# 03-Actuators.net
KiCad netlist of a schematic drawn in Altium Designer
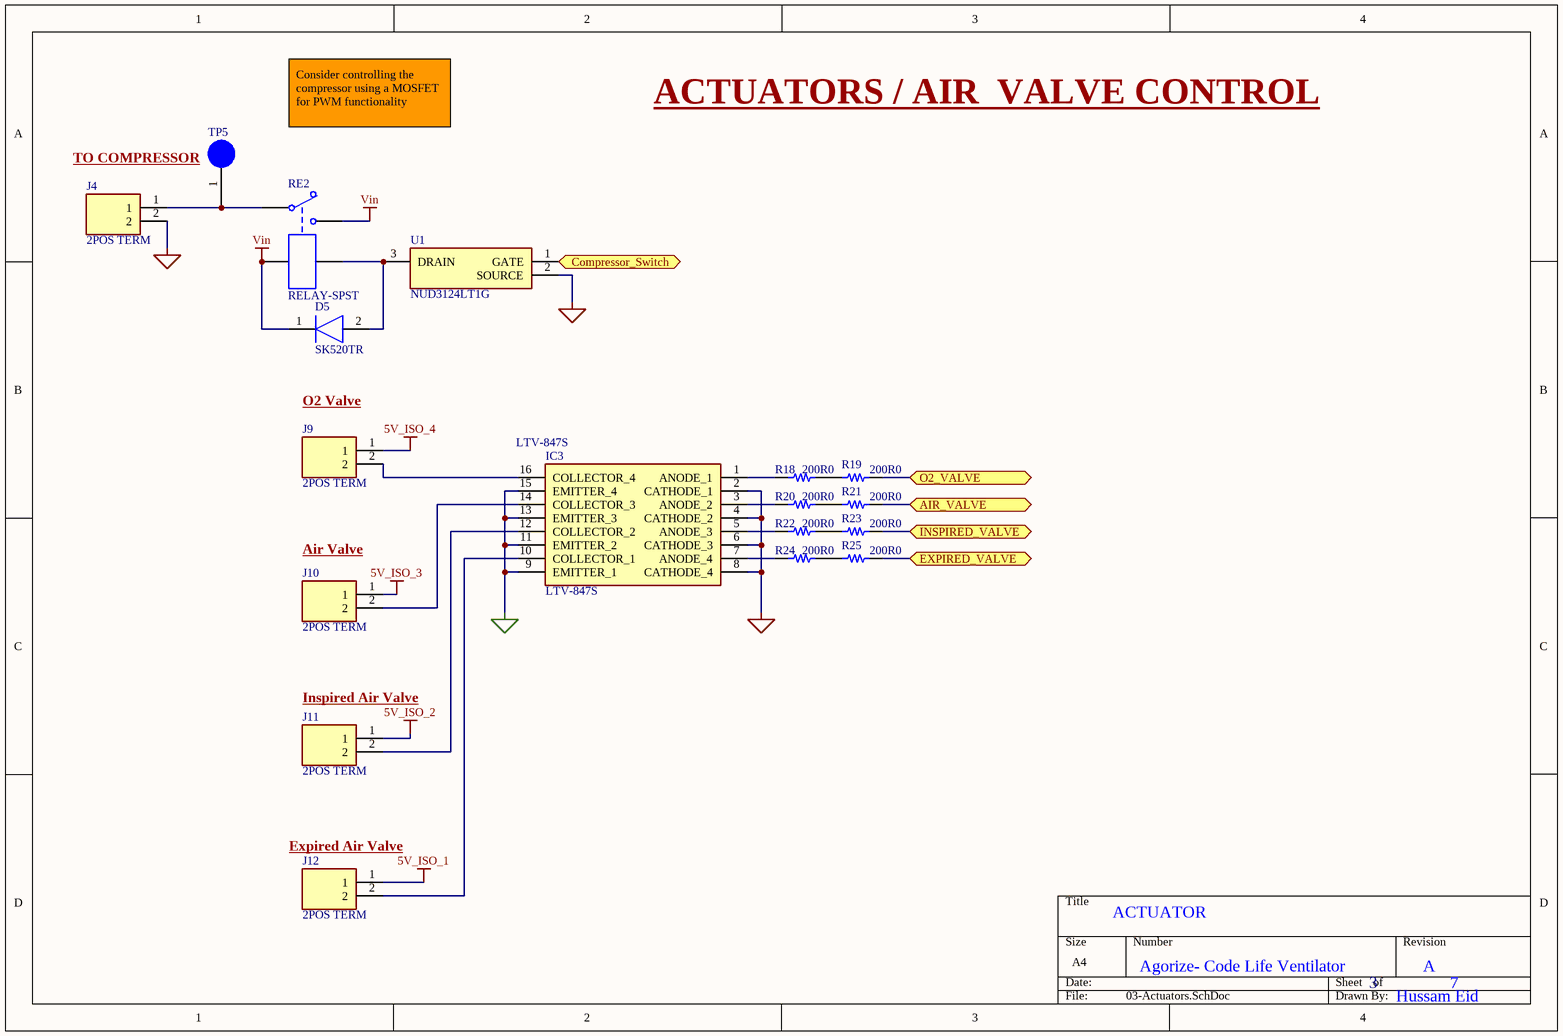
[diagram p0: 03-Actuators.SchDoc]

(export (version "E")
  (design (tool "Eeschema 10.0.6"))
  (components
    (comp (ref "D5")
      (value "SK520TR")
      (footprint "SamacSys:DIOM8060X295N")
      (description "DIODE SCHOTTKY 200V 5A SMC")
      (libsource (lib "*") (part "SK520TR"))
    )
    (comp (ref "IC3")
      (value "LTV-847S")
      (footprint "SamacSys:SOP254P1031X450-16N")
      (description "OPTOISOLTR 5KV 4CH TRANS 16-SMD")
      (fields (field (name "MANUFACTURER PART NUMBER 1") "LTV-847S"))
      (libsource (lib "*") (part "LTV-847S"))
    )
    (comp (ref "J4")
      (value "2POS TERM")
      (footprint "PcbLib1:SHDR2W110P0X500_1X2_1000X830X1140P")
      (description "TERM BLK 2POS SIDE ENTRY 5MM PCB")
      (fields (field (name "VOLTAGE") "300V"))
      (libsource (lib "*") (part "1935161"))
    )
    (comp (ref "J9")
      (value "2POS TERM")
      (footprint "PcbLib1:SHDR2W110P0X500_1X2_1000X830X1140P")
      (description "TERM BLK 2POS SIDE ENTRY 5MM PCB")
      (fields (field (name "VOLTAGE") "300V"))
      (libsource (lib "*") (part "1935161"))
    )
    (comp (ref "J10")
      (value "2POS TERM")
      (footprint "PcbLib1:SHDR2W110P0X500_1X2_1000X830X1140P")
      (description "TERM BLK 2POS SIDE ENTRY 5MM PCB")
      (fields (field (name "VOLTAGE") "300V"))
      (libsource (lib "*") (part "1935161"))
    )
    (comp (ref "J11")
      (value "2POS TERM")
      (footprint "PcbLib1:SHDR2W110P0X500_1X2_1000X830X1140P")
      (description "TERM BLK 2POS SIDE ENTRY 5MM PCB")
      (fields (field (name "VOLTAGE") "300V"))
      (libsource (lib "*") (part "1935161"))
    )
    (comp (ref "J12")
      (value "2POS TERM")
      (footprint "PcbLib1:SHDR2W110P0X500_1X2_1000X830X1140P")
      (description "TERM BLK 2POS SIDE ENTRY 5MM PCB")
      (fields (field (name "VOLTAGE") "300V"))
      (libsource (lib "*") (part "1935161"))
    )
    (comp (ref "R18")
      (value "200R0")
      (footprint "RES 1206/3216")
      (description "RES SMD 10K OHM 1% 1/4W 1206")
      (fields (field (name "TOLERANCE") "1%"))
      (libsource (lib "Celestial Library Database") (part "Resistor"))
    )
    (comp (ref "R19")
      (value "200R0")
      (footprint "RES 1206/3216")
      (description "RES SMD 10K OHM 1% 1/4W 1206")
      (fields (field (name "TOLERANCE") "1%"))
      (libsource (lib "Celestial Library Database") (part "Resistor"))
    )
    (comp (ref "R20")
      (value "200R0")
      (footprint "RES 1206/3216")
      (description "RES SMD 10K OHM 1% 1/4W 1206")
      (fields (field (name "TOLERANCE") "1%"))
      (libsource (lib "Celestial Library Database") (part "Resistor"))
    )
    (comp (ref "R21")
      (value "200R0")
      (footprint "RES 1206/3216")
      (description "RES SMD 10K OHM 1% 1/4W 1206")
      (fields (field (name "TOLERANCE") "1%"))
      (libsource (lib "Celestial Library Database") (part "Resistor"))
    )
    (comp (ref "R22")
      (value "200R0")
      (footprint "RES 1206/3216")
      (description "RES SMD 10K OHM 1% 1/4W 1206")
      (fields (field (name "TOLERANCE") "1%"))
      (libsource (lib "Celestial Library Database") (part "Resistor"))
    )
    (comp (ref "R23")
      (value "200R0")
      (footprint "RES 1206/3216")
      (description "RES SMD 10K OHM 1% 1/4W 1206")
      (fields (field (name "TOLERANCE") "1%"))
      (libsource (lib "Celestial Library Database") (part "Resistor"))
    )
    (comp (ref "R24")
      (value "200R0")
      (footprint "RES 1206/3216")
      (description "RES SMD 10K OHM 1% 1/4W 1206")
      (fields (field (name "TOLERANCE") "1%"))
      (libsource (lib "Celestial Library Database") (part "Resistor"))
    )
    (comp (ref "R25")
      (value "200R0")
      (footprint "RES 1206/3216")
      (description "RES SMD 10K OHM 1% 1/4W 1206")
      (fields (field (name "TOLERANCE") "1%"))
      (libsource (lib "Celestial Library Database") (part "Resistor"))
    )
    (comp (ref "RE2")
      (value "RELAY-SPST")
      (footprint "JSM1A12V4")
      (description "RELAY AUTOMOTIVE SPST 15A 12V")
      (libsource (lib "Schlib1") (part "RELAY-SPST"))
    )
    (comp (ref "TP5")
      (value "TP")
      (footprint "TP")
      (description "Test Point")
      (libsource (lib "Schlib1") (part "TP"))
    )
    (comp (ref "U1")
      (value "NUD3124LT1G")
      (footprint "SamacSys:SOT96P237X111-3N")
      (description "IC PWR DRVR N-CHAN 1:1 SOT23-3")
      (libsource (lib "*") (part "NUD3124LT1G"))
    )
  )
  (nets
    (net (code "1") (name "/AIR_VALVE") (class "Default")
      (node (ref "R21") (pin "1") (pinfunction "1_1") (pintype "passive"))
    )
    (net (code "2") (name "/Compressor_Switch") (class "Default")
      (node (ref "U1") (pin "1") (pinfunction "GATE_1") (pintype "passive"))
    )
    (net (code "3") (name "/EXPIRED_VALVE") (class "Default")
      (node (ref "R25") (pin "1") (pinfunction "1_1") (pintype "passive"))
    )
    (net (code "4") (name "/INSPIRED_VALVE") (class "Default")
      (node (ref "R23") (pin "1") (pinfunction "1_1") (pintype "passive"))
    )
    (net (code "5") (name "/O2_VALVE") (class "Default")
      (node (ref "R19") (pin "1") (pinfunction "1_1") (pintype "passive"))
    )
    (net (code "6") (name "5V_ISO_1") (class "Default")
      (node (ref "J12") (pin "1") (pinfunction "1_1") (pintype "passive"))
    )
    (net (code "7") (name "5V_ISO_2") (class "Default")
      (node (ref "J11") (pin "1") (pinfunction "1_1") (pintype "passive"))
    )
    (net (code "8") (name "5V_ISO_3") (class "Default")
      (node (ref "J10") (pin "1") (pinfunction "1_1") (pintype "passive"))
    )
    (net (code "9") (name "5V_ISO_4") (class "Default")
      (node (ref "J9") (pin "1") (pinfunction "1_1") (pintype "passive"))
    )
    (net (code "10") (name "COM") (class "Default")
      (node (ref "IC3") (pin "2") (pinfunction "CATHODE_1_2") (pintype "passive"))
      (node (ref "IC3") (pin "4") (pinfunction "CATHODE_2_4") (pintype "passive"))
      (node (ref "IC3") (pin "6") (pinfunction "CATHODE_3_6") (pintype "passive"))
      (node (ref "IC3") (pin "8") (pinfunction "CATHODE_4_8") (pintype "passive"))
      (node (ref "J4") (pin "2") (pinfunction "2_2") (pintype "passive"))
      (node (ref "U1") (pin "2") (pinfunction "SOURCE_2") (pintype "passive"))
    )
    (net (code "11") (name "COM_ISO") (class "Default")
      (node (ref "IC3") (pin "11") (pinfunction "EMITTER_2_11") (pintype "passive"))
      (node (ref "IC3") (pin "13") (pinfunction "EMITTER_3_13") (pintype "passive"))
      (node (ref "IC3") (pin "15") (pinfunction "EMITTER_4_15") (pintype "passive"))
      (node (ref "IC3") (pin "9") (pinfunction "EMITTER_1_9") (pintype "passive"))
    )
    (net (code "12") (name "Net-(D5-A)") (class "Default")
      (node (ref "D5") (pin "2") (pinfunction "A_2") (pintype "passive"))
      (node (ref "RE2") (pin "5") (pinfunction "5_5") (pintype "passive"))
      (node (ref "U1") (pin "3") (pinfunction "DRAIN_3") (pintype "passive"))
    )
    (net (code "13") (name "Net-(IC3-ANODE_1)") (class "Default")
      (node (ref "IC3") (pin "1") (pinfunction "ANODE_1_1") (pintype "passive"))
      (node (ref "R18") (pin "2") (pinfunction "2_2") (pintype "passive"))
    )
    (net (code "14") (name "Net-(IC3-ANODE_2)") (class "Default")
      (node (ref "IC3") (pin "3") (pinfunction "ANODE_2_3") (pintype "passive"))
      (node (ref "R20") (pin "2") (pinfunction "2_2") (pintype "passive"))
    )
    (net (code "15") (name "Net-(IC3-ANODE_3)") (class "Default")
      (node (ref "IC3") (pin "5") (pinfunction "ANODE_3_5") (pintype "passive"))
      (node (ref "R22") (pin "2") (pinfunction "2_2") (pintype "passive"))
    )
    (net (code "16") (name "Net-(IC3-ANODE_4)") (class "Default")
      (node (ref "IC3") (pin "7") (pinfunction "ANODE_4_7") (pintype "passive"))
      (node (ref "R24") (pin "2") (pinfunction "2_2") (pintype "passive"))
    )
    (net (code "17") (name "Net-(IC3-COLLECTOR_1)") (class "Default")
      (node (ref "IC3") (pin "10") (pinfunction "COLLECTOR_1_10") (pintype "passive"))
      (node (ref "J12") (pin "2") (pinfunction "2_2") (pintype "passive"))
    )
    (net (code "18") (name "Net-(IC3-COLLECTOR_2)") (class "Default")
      (node (ref "IC3") (pin "12") (pinfunction "COLLECTOR_2_12") (pintype "passive"))
      (node (ref "J11") (pin "2") (pinfunction "2_2") (pintype "passive"))
    )
    (net (code "19") (name "Net-(IC3-COLLECTOR_3)") (class "Default")
      (node (ref "IC3") (pin "14") (pinfunction "COLLECTOR_3_14") (pintype "passive"))
      (node (ref "J10") (pin "2") (pinfunction "2_2") (pintype "passive"))
    )
    (net (code "20") (name "Net-(IC3-COLLECTOR_4)") (class "Default")
      (node (ref "IC3") (pin "16") (pinfunction "COLLECTOR_4_16") (pintype "passive"))
      (node (ref "J9") (pin "2") (pinfunction "2_2") (pintype "passive"))
    )
    (net (code "21") (name "Net-(J4-Pad1)") (class "Default")
      (node (ref "J4") (pin "1") (pinfunction "1_1") (pintype "passive"))
      (node (ref "RE2") (pin "1") (pinfunction "1_1") (pintype "passive"))
      (node (ref "TP5") (pin "1") (pinfunction "1_1") (pintype "passive"))
    )
    (net (code "22") (name "Net-(R18-Pad1)") (class "Default")
      (node (ref "R18") (pin "1") (pinfunction "1_1") (pintype "passive"))
      (node (ref "R19") (pin "2") (pinfunction "2_2") (pintype "passive"))
    )
    (net (code "23") (name "Net-(R20-Pad1)") (class "Default")
      (node (ref "R20") (pin "1") (pinfunction "1_1") (pintype "passive"))
      (node (ref "R21") (pin "2") (pinfunction "2_2") (pintype "passive"))
    )
    (net (code "24") (name "Net-(R22-Pad1)") (class "Default")
      (node (ref "R22") (pin "1") (pinfunction "1_1") (pintype "passive"))
      (node (ref "R23") (pin "2") (pinfunction "2_2") (pintype "passive"))
    )
    (net (code "25") (name "Net-(R24-Pad1)") (class "Default")
      (node (ref "R24") (pin "1") (pinfunction "1_1") (pintype "passive"))
      (node (ref "R25") (pin "2") (pinfunction "2_2") (pintype "passive"))
    )
    (net (code "26") (name "Vin") (class "Default")
      (node (ref "D5") (pin "1") (pinfunction "K_1") (pintype "passive"))
      (node (ref "RE2") (pin "2") (pinfunction "2_2") (pintype "passive"))
      (node (ref "RE2") (pin "3") (pinfunction "3_3") (pintype "passive"))
    )
  )
)
